# POWER_SUPPLY.net
KiCad netlist of a schematic drawn in Altium Designer
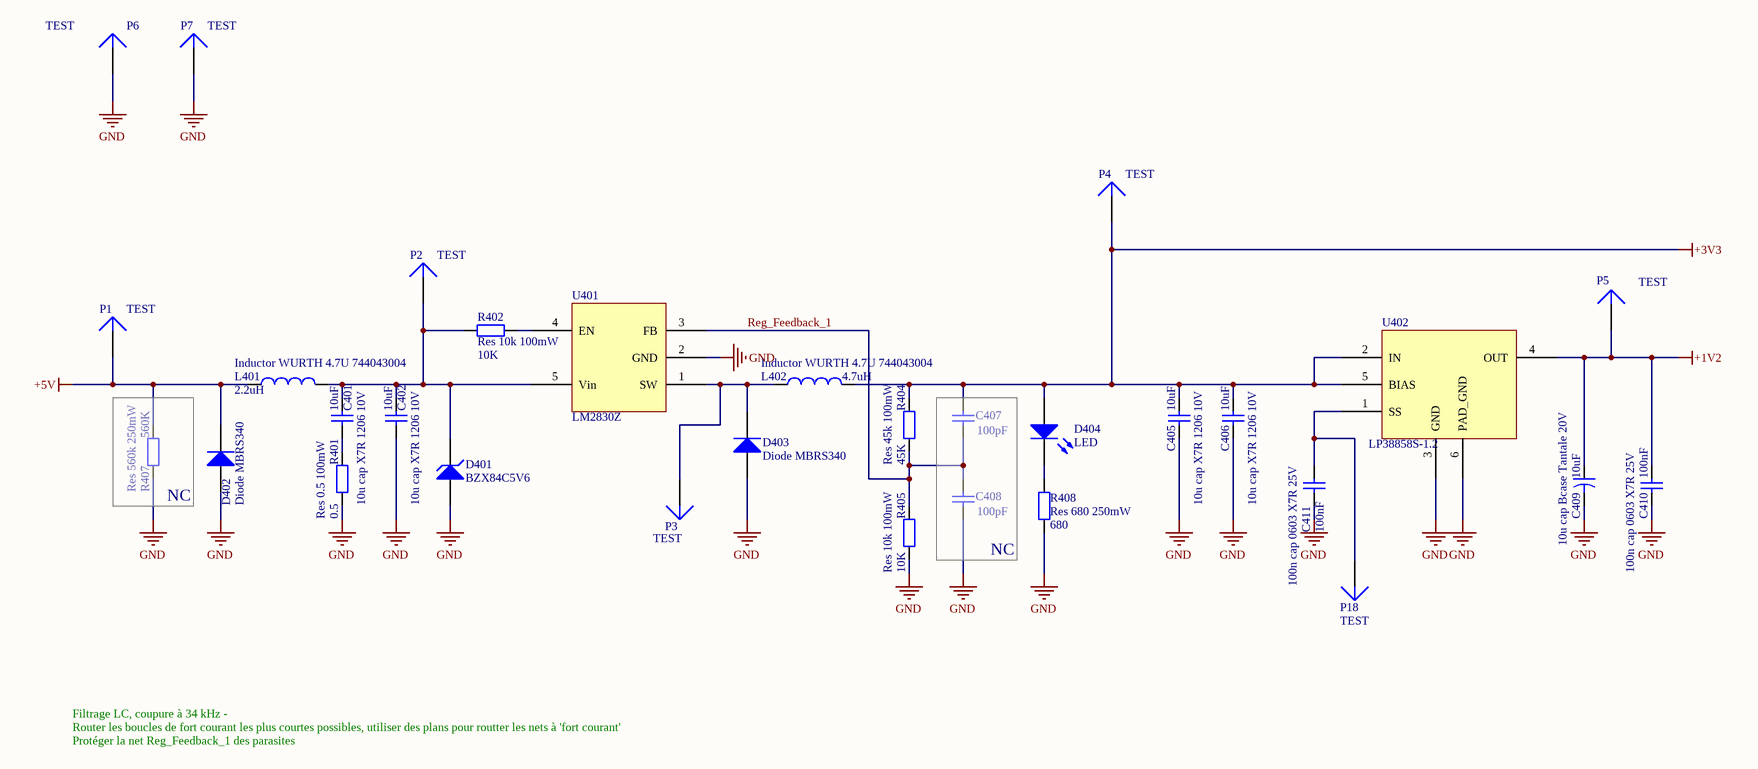
[diagram p0: POWER_SUPPLY.SchDoc]

(export (version "E")
  (design (tool "Eeschema 10.0.6"))
  (components
    (comp (ref "C401")
      (value "10u cap X7R 1206 10V")
      (footprint "3216[1206]")
      (description "Capacitor")
      (fields (field (name "ALTIUM_VALUE") "10uF") (field (name "PUBLISHER") "Altium Limited"))
      (libsource (lib "Miscellaneous Devices") (part "Cap"))
    )
    (comp (ref "C402")
      (value "10u cap X7R 1206 10V")
      (footprint "3216[1206]")
      (description "Capacitor")
      (fields (field (name "ALTIUM_VALUE") "10uF") (field (name "PUBLISHER") "Altium Limited"))
      (libsource (lib "Miscellaneous Devices") (part "Cap"))
    )
    (comp (ref "C405")
      (value "10u cap X7R 1206 10V")
      (footprint "3216[1206]")
      (description "Capacitor")
      (fields (field (name "ALTIUM_VALUE") "10uF") (field (name "PUBLISHER") "Altium Limited"))
      (libsource (lib "Miscellaneous Devices") (part "Cap"))
    )
    (comp (ref "C406")
      (value "10u cap X7R 1206 10V")
      (footprint "3216[1206]")
      (description "Capacitor")
      (fields (field (name "ALTIUM_VALUE") "10uF") (field (name "PUBLISHER") "Altium Limited"))
      (libsource (lib "Miscellaneous Devices") (part "Cap"))
    )
    (comp (ref "C407")
      (value "100pF")
      (footprint "1608[0603]")
      (description "Capacitor")
      (fields (field (name "Comment") "100p cap 0603 X7R 25V") (field (name "PUBLISHER") "Altium Limited"))
      (libsource (lib "Miscellaneous Devices") (part "Cap"))
    )
    (comp (ref "C408")
      (value "100pF")
      (footprint "1608[0603]")
      (description "Capacitor")
      (fields (field (name "Comment") "100p cap 0603 X7R 25V") (field (name "PUBLISHER") "Altium Limited"))
      (libsource (lib "Miscellaneous Devices") (part "Cap"))
    )
    (comp (ref "C409")
      (value "10u cap Bcase Tantale 20V")
      (footprint "6032")
      (description "Capacitor")
      (fields (field (name "ALTIUM_VALUE") "10uF") (field (name "PUBLISHER") "Altium Limited"))
      (libsource (lib "Miscellaneous Devices") (part "Cap2"))
    )
    (comp (ref "C410")
      (value "100n cap 0603 X7R 25V")
      (footprint "1608[0603]")
      (description "Capacitor")
      (fields (field (name "ALTIUM_VALUE") "100nF") (field (name "PUBLISHER") "Altium Limited"))
      (libsource (lib "Miscellaneous Devices") (part "Cap"))
    )
    (comp (ref "C411")
      (value "100n cap 0603 X7R 25V")
      (footprint "1608[0603]")
      (description "Capacitor")
      (fields (field (name "ALTIUM_VALUE") "100nF") (field (name "PUBLISHER") "Altium Limited"))
      (libsource (lib "Miscellaneous Devices") (part "Cap"))
    )
    (comp (ref "D401")
      (value "BZX84C5V6")
      (footprint "318-07")
      (description "Zener Voltage Regulator Diode")
      (fields (field (name "PUBLISHER") "Altium Limited"))
      (libsource (lib "Motorola Discrete Diode") (part "BZX84C5V6LT1"))
    )
    (comp (ref "D402")
      (value "Diode MBRS340")
      (footprint "SMC")
      (description "SCHOTTKY 3A DIODE")
      (fields (field (name "PUBLISHER") "Altium Limited"))
      (libsource (lib "Miscellaneous Devices") (part "Diode"))
    )
    (comp (ref "D403")
      (value "Diode MBRS340")
      (footprint "SMC")
      (description "SCHOTTKY 3A DIODE")
      (fields (field (name "PUBLISHER") "Altium Limited"))
      (libsource (lib "Miscellaneous Devices") (part "Diode"))
    )
    (comp (ref "D404")
      (value "LED")
      (footprint "1608[0603]")
      (description "LED SML-311DTT86")
      (fields (field (name "PUBLISHER") "Altium Limited"))
      (libsource (lib "Miscellaneous Devices") (part "LED0"))
    )
    (comp (ref "L401")
      (value "Inductor WURTH 4.7U 744043004")
      (footprint "744043004")
      (description "Inductor")
      (fields (field (name "ALTIUM_VALUE") "2.2uH") (field (name "PUBLISHER") "Altium Limited"))
      (libsource (lib "Miscellaneous Devices") (part "Inductor"))
    )
    (comp (ref "L402")
      (value "Inductor WURTH 4.7U 744043004")
      (footprint "744043004")
      (description "Inductor")
      (fields (field (name "ALTIUM_VALUE") "4.7uH") (field (name "PUBLISHER") "Altium Limited"))
      (libsource (lib "Miscellaneous Devices") (part "Inductor"))
    )
    (comp (ref "P1")
      (value "TEST")
      (footprint "TP1")
      (description "Plug")
      (fields (field (name "PUBLISHER") "Altium Limited"))
      (libsource (lib "Miscellaneous Connectors") (part "Plug"))
    )
    (comp (ref "P2")
      (value "TEST")
      (footprint "TP1")
      (description "Plug")
      (fields (field (name "PUBLISHER") "Altium Limited"))
      (libsource (lib "Miscellaneous Connectors") (part "Plug"))
    )
    (comp (ref "P3")
      (value "TEST")
      (footprint "TP1")
      (description "Plug")
      (fields (field (name "PUBLISHER") "Altium Limited"))
      (libsource (lib "Miscellaneous Connectors") (part "Plug"))
    )
    (comp (ref "P4")
      (value "TEST")
      (footprint "TP1")
      (description "Plug")
      (fields (field (name "PUBLISHER") "Altium Limited"))
      (libsource (lib "Miscellaneous Connectors") (part "Plug"))
    )
    (comp (ref "P5")
      (value "TEST")
      (footprint "TP1")
      (description "Plug")
      (fields (field (name "PUBLISHER") "Altium Limited"))
      (libsource (lib "Miscellaneous Connectors") (part "Plug"))
    )
    (comp (ref "P6")
      (value "TEST")
      (footprint "PIN1")
      (description "Plug")
      (fields (field (name "PUBLISHER") "Altium Limited"))
      (libsource (lib "Miscellaneous Connectors") (part "Plug"))
    )
    (comp (ref "P7")
      (value "TEST")
      (footprint "PIN1")
      (description "Plug")
      (fields (field (name "PUBLISHER") "Altium Limited"))
      (libsource (lib "Miscellaneous Connectors") (part "Plug"))
    )
    (comp (ref "P18")
      (value "TEST")
      (footprint "TP1")
      (description "Plug")
      (fields (field (name "PUBLISHER") "Altium Limited"))
      (libsource (lib "Miscellaneous Connectors") (part "Plug"))
    )
    (comp (ref "R401")
      (value "Res 0.5 100mW")
      (footprint "1608[0603]")
      (description "Resistor")
      (fields (field (name "ALTIUM_VALUE") "0.5") (field (name "PUBLISHER") "Altium Limited"))
      (libsource (lib "Miscellaneous Devices") (part "Res2"))
    )
    (comp (ref "R402")
      (value "Res 10k 100mW")
      (footprint "1608[0603]")
      (description "Resistor")
      (fields (field (name "ALTIUM_VALUE") "10K") (field (name "PUBLISHER") "Altium Limited"))
      (libsource (lib "") (part "Res2_1"))
    )
    (comp (ref "R404")
      (value "Res 45k 100mW")
      (footprint "1608[0603]")
      (description "Resistor")
      (fields (field (name "ALTIUM_VALUE") "45K") (field (name "PUBLISHER") "Altium Limited"))
      (libsource (lib "Miscellaneous Devices") (part "Res2"))
    )
    (comp (ref "R405")
      (value "Res 10k 100mW")
      (footprint "1608[0603]")
      (description "Resistor")
      (fields (field (name "ALTIUM_VALUE") "10K") (field (name "PUBLISHER") "Altium Limited"))
      (libsource (lib "Miscellaneous Devices") (part "Res2"))
    )
    (comp (ref "R407")
      (value "Res 560k 250mW")
      (footprint "3216[1206]")
      (description "Resistor")
      (fields (field (name "ALTIUM_VALUE") "560K") (field (name "PUBLISHER") "Altium Limited"))
      (libsource (lib "Miscellaneous Devices") (part "Res2"))
    )
    (comp (ref "R408")
      (value "Res 680 250mW")
      (footprint "1608[0603]")
      (description "Resistor")
      (fields (field (name "ALTIUM_VALUE") "680") (field (name "PUBLISHER") "Altium Limited"))
      (libsource (lib "Miscellaneous Devices") (part "Res2"))
    )
    (comp (ref "U401")
      (value "LM2830Z")
      (footprint "DBV005")
      (description "High Frequency 1.0A Load - Step-Down DC-DC Regulator")
      (libsource (lib "pic32USB") (part "LM2830"))
    )
    (comp (ref "U402")
      (value "LP38858S-1.2")
      (footprint "TO263-5Lead")
      (description "1.5A Fast-Reponse High-Accuracy LDO Linear Regulator with Soft-Start")
      (libsource (lib "pic32USB") (part "LP38858"))
    )
  )
  (nets
    (net (code "1") (name "+1V2") (class "Default")
      (node (ref "C409") (pin "1") (pinfunction "1_1") (pintype "passive"))
      (node (ref "C410") (pin "2") (pinfunction "2_2") (pintype "passive"))
      (node (ref "P5") (pin "1") (pinfunction "1_1") (pintype "passive"))
      (node (ref "U402") (pin "4") (pinfunction "OUT_4") (pintype "passive"))
    )
    (net (code "2") (name "+3V3") (class "Default")
      (node (ref "C405") (pin "2") (pinfunction "2_2") (pintype "passive"))
      (node (ref "C406") (pin "2") (pinfunction "2_2") (pintype "passive"))
      (node (ref "C407") (pin "2") (pinfunction "2_2") (pintype "passive"))
      (node (ref "D404") (pin "1") (pinfunction "A_1") (pintype "passive"))
      (node (ref "L402") (pin "2") (pinfunction "2_2") (pintype "passive"))
      (node (ref "P4") (pin "1") (pinfunction "1_1") (pintype "passive"))
      (node (ref "R404") (pin "2") (pinfunction "2_2") (pintype "passive"))
      (node (ref "U402") (pin "2") (pinfunction "IN_2") (pintype "passive"))
      (node (ref "U402") (pin "5") (pinfunction "BIAS_5") (pintype "passive"))
    )
    (net (code "3") (name "+5V") (class "Default")
      (node (ref "D402") (pin "2") (pinfunction "K_2") (pintype "passive"))
      (node (ref "L401") (pin "1") (pinfunction "1_1") (pintype "passive"))
      (node (ref "P1") (pin "1") (pinfunction "1_1") (pintype "passive"))
      (node (ref "R407") (pin "2") (pinfunction "2_2") (pintype "passive"))
    )
    (net (code "4") (name "/Reg_Feedback_1") (class "Default")
      (node (ref "C407") (pin "1") (pinfunction "1_1") (pintype "passive"))
      (node (ref "C408") (pin "2") (pinfunction "2_2") (pintype "passive"))
      (node (ref "R404") (pin "1") (pinfunction "1_1") (pintype "passive"))
      (node (ref "R405") (pin "2") (pinfunction "2_2") (pintype "passive"))
      (node (ref "U401") (pin "3") (pinfunction "FB_3") (pintype "passive"))
    )
    (net (code "5") (name "GND") (class "Default")
      (node (ref "C402") (pin "1") (pinfunction "1_1") (pintype "passive"))
      (node (ref "C405") (pin "1") (pinfunction "1_1") (pintype "passive"))
      (node (ref "C406") (pin "1") (pinfunction "1_1") (pintype "passive"))
      (node (ref "C408") (pin "1") (pinfunction "1_1") (pintype "passive"))
      (node (ref "C409") (pin "2") (pinfunction "2_2") (pintype "passive"))
      (node (ref "C410") (pin "1") (pinfunction "1_1") (pintype "passive"))
      (node (ref "C411") (pin "1") (pinfunction "1_1") (pintype "passive"))
      (node (ref "D401") (pin "1") (pinfunction "A_1") (pintype "passive"))
      (node (ref "D402") (pin "1") (pinfunction "A_1") (pintype "passive"))
      (node (ref "D403") (pin "1") (pinfunction "A_1") (pintype "passive"))
      (node (ref "P6") (pin "1") (pinfunction "1_1") (pintype "passive"))
      (node (ref "P7") (pin "1") (pinfunction "1_1") (pintype "passive"))
      (node (ref "R401") (pin "1") (pinfunction "1_1") (pintype "passive"))
      (node (ref "R405") (pin "1") (pinfunction "1_1") (pintype "passive"))
      (node (ref "R407") (pin "1") (pinfunction "1_1") (pintype "passive"))
      (node (ref "R408") (pin "1") (pinfunction "1_1") (pintype "passive"))
      (node (ref "U401") (pin "2") (pinfunction "GND_2") (pintype "passive"))
      (node (ref "U402") (pin "3") (pinfunction "GND_3") (pintype "passive"))
      (node (ref "U402") (pin "6") (pinfunction "PAD_GND_6") (pintype "passive"))
    )
    (net (code "6") (name "Net-(C401-Pad1)") (class "Default")
      (node (ref "C401") (pin "1") (pinfunction "1_1") (pintype "passive"))
      (node (ref "R401") (pin "2") (pinfunction "2_2") (pintype "passive"))
    )
    (net (code "7") (name "Net-(D401-K)") (class "Default")
      (node (ref "C401") (pin "2") (pinfunction "2_2") (pintype "passive"))
      (node (ref "C402") (pin "2") (pinfunction "2_2") (pintype "passive"))
      (node (ref "D401") (pin "3") (pinfunction "K_3") (pintype "passive"))
      (node (ref "L401") (pin "2") (pinfunction "2_2") (pintype "passive"))
      (node (ref "P2") (pin "1") (pinfunction "1_1") (pintype "passive"))
      (node (ref "R402") (pin "1") (pinfunction "1_1") (pintype "passive"))
      (node (ref "U401") (pin "5") (pinfunction "Vin_5") (pintype "passive"))
    )
    (net (code "8") (name "Net-(D403-K)") (class "Default")
      (node (ref "D403") (pin "2") (pinfunction "K_2") (pintype "passive"))
      (node (ref "L402") (pin "1") (pinfunction "1_1") (pintype "passive"))
      (node (ref "P3") (pin "1") (pinfunction "1_1") (pintype "passive"))
      (node (ref "U401") (pin "1") (pinfunction "SW_1") (pintype "passive"))
    )
    (net (code "9") (name "Net-(D404-K)") (class "Default")
      (node (ref "D404") (pin "2") (pinfunction "K_2") (pintype "passive"))
      (node (ref "R408") (pin "2") (pinfunction "2_2") (pintype "passive"))
    )
    (net (code "10") (name "Net-(U401-EN)") (class "Default")
      (node (ref "R402") (pin "2") (pinfunction "2_2") (pintype "passive"))
      (node (ref "U401") (pin "4") (pinfunction "EN_4") (pintype "passive"))
    )
    (net (code "11") (name "Net-(U402-SS)") (class "Default")
      (node (ref "C411") (pin "2") (pinfunction "2_2") (pintype "passive"))
      (node (ref "P18") (pin "1") (pinfunction "1_1") (pintype "passive"))
      (node (ref "U402") (pin "1") (pinfunction "SS_1") (pintype "passive"))
    )
  )
)
